# 01_-ATMEGA328.net
KiCad netlist of a schematic drawn in Altium Designer
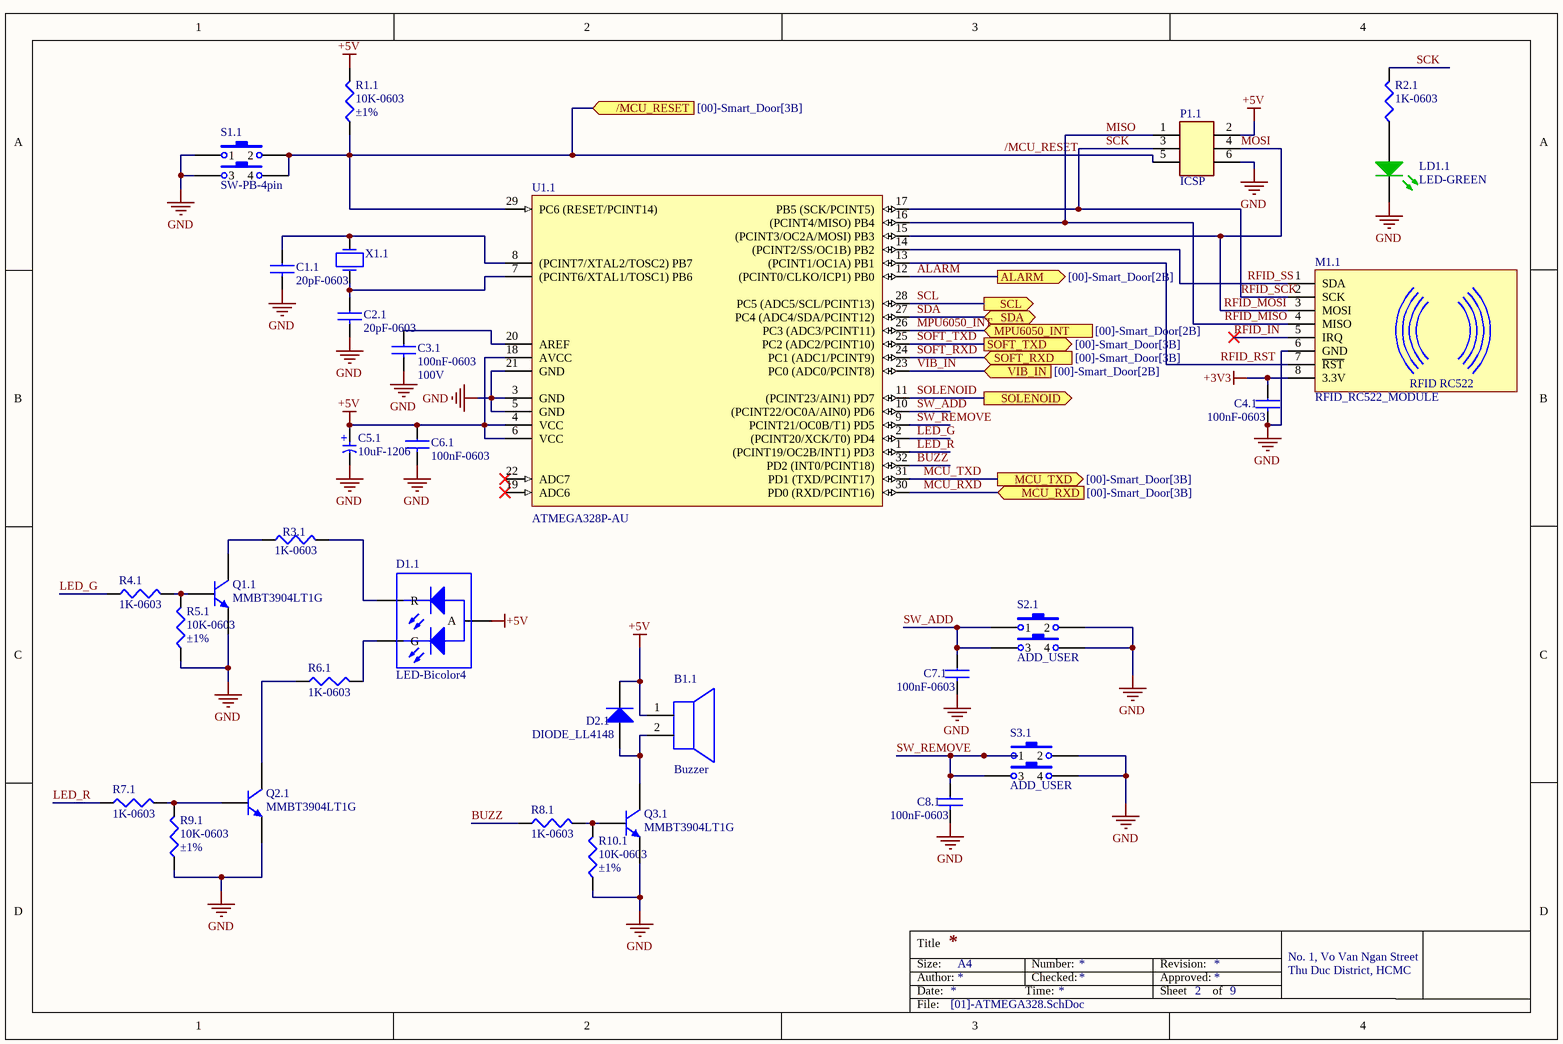
[diagram p0: [01]-ATMEGA328.SchDoc]

(export (version "E")
  (design (tool "Eeschema 10.0.6"))
  (components
    (comp (ref "B1.1")
      (value "Buzzer")
      (footprint "MinhTien_PcbLib:Buzzer")
      (libsource (lib "MinhTien_SCHLib") (part "Buzzer"))
    )
    (comp (ref "C1.1")
      (value "20pF-0603")
      (footprint "CAP0603")
      (description "CAP CER 20PF 50V C0G/NPO 0603")
      (fields (field (name "TOLERANCE") "±5%"))
      (libsource (lib "Indruino") (part "CC0603JRNPO9BN200"))
    )
    (comp (ref "C2.1")
      (value "20pF-0603")
      (footprint "CAP0603")
      (description "CAP CER 20PF 50V C0G/NPO 0603")
      (fields (field (name "TOLERANCE") "±5%"))
      (libsource (lib "Indruino") (part "CC0603JRNPO9BN200"))
    )
    (comp (ref "C3.1")
      (value "100nF-0603")
      (footprint "CAP0603")
      (description "CAP CER 0.1UF 100V X7R 0603")
      (fields
        (field (name "MANUFACTURER") "Yageo")
        (field (name "MANUFACTURER PART NUMBER") "CC0603KRX7R0BB104")
        (field (name "VOLTAGE - RATED") "100V")
      )
      (libsource (lib "Indruino") (part "CC0603KRX7R0BB104"))
    )
    (comp (ref "C4.1")
      (value "100nF-0603")
      (footprint "CAP0603")
      (description "CAP CER 0.1UF 50V X7R 0603")
      (fields (field (name "TOLERANCE") "±10%"))
      (libsource (lib "Indruino") (part "CC0603KRX7R9BB104"))
    )
    (comp (ref "C5.1")
      (value "10uF-1206")
      (footprint "AZ_Lib:CAP1206_TANT")
      (description "Cap Tant Solid 10uF 16V A CASE 10% (3.2 X 1.6 X 1.6mm) Inward L SMD 3216-18 3 Ohm 125C T/R")
      (fields (field (name "TOLERANCE") "10%") (field (name "VOLTAGE") "16V"))
      (libsource (lib "AZ_Lib") (part "T491A106K016AT"))
    )
    (comp (ref "C6.1")
      (value "100nF-0603")
      (footprint "CAP0603")
      (description "CAP CER 0.1UF 100V X7R 0603")
      (fields
        (field (name "MANUFACTURER") "Yageo")
        (field (name "MANUFACTURER PART NUMBER") "CC0603KRX7R0BB104")
      )
      (libsource (lib "Indruino") (part "CC0603KRX7R0BB104"))
    )
    (comp (ref "C7.1")
      (value "100nF-0603")
      (footprint "CAP0603")
      (description "CAP CER 0.1UF 50V X7R 0603")
      (fields (field (name "TOLERANCE") "±10%"))
      (libsource (lib "Indruino") (part "CC0603KRX7R9BB104"))
    )
    (comp (ref "C8.1")
      (value "100nF-0603")
      (footprint "CAP0603")
      (description "CAP CER 0.1UF 50V X7R 0603")
      (fields (field (name "TOLERANCE") "±10%"))
      (libsource (lib "Indruino") (part "CC0603KRX7R9BB104"))
    )
    (comp (ref "D1.1")
      (value "LED-Bicolor4")
      (footprint "MinhTien_PcbLib:LED_3mm-Bicolor")
      (description "Common Anode")
      (fields (field (name "PUBLISHER") "Altium Limited"))
      (libsource (lib "MinhTien_SCHLib") (part "LED-Bicolor4"))
    )
    (comp (ref "D2.1")
      (value "DIODE_LL4148")
      (footprint "Indruino:SOD80")
      (description "DIODE GEN PURP 100V 200MA SOD80")
      (fields
        (field (name "MANUFACTURER") "Fairchild/ON Semiconductor")
        (field (name "MANUFACTURER PART NUMBER") "LL4148")
      )
      (libsource (lib "Indruino") (part "DIODE_LL4148"))
    )
    (comp (ref "LD1.1")
      (value "LED-GREEN")
      (footprint "Indruino:LED_SMD0603_GREEN")
      (description "LED GREEN CLEAR 0603 SMD")
      (libsource (lib "Indruino") (part "LED_LTST-C191KGKT"))
    )
    (comp (ref "M1.1")
      (value "RFID_RC522_MODULE")
      (footprint "AZ_Lib:RFID_RC522_MODULE")
      (libsource (lib "AZ_Lib") (part "RFID_RC522_MODULE"))
    )
    (comp (ref "P1.1")
      (value "ICSP")
      (footprint "AZ_Lib:HDR3X2_2.54_MALE")
      (description "Header 3x2 pins male, pitch 2.54mm")
      (libsource (lib "AZ_Lib") (part "HDR3X2_2.54_MALE"))
    )
    (comp (ref "Q1.1")
      (value "MMBT3904LT1G")
      (footprint "Indruino:SOT23-3")
      (description "TRANS NPN 40V 0.2A SOT23")
      (libsource (lib "Indruino") (part "MMBT3904LT1G"))
    )
    (comp (ref "Q2.1")
      (value "MMBT3904LT1G")
      (footprint "Indruino:SOT23-3")
      (description "TRANS NPN 40V 0.2A SOT23")
      (libsource (lib "Indruino") (part "MMBT3904LT1G"))
    )
    (comp (ref "Q3.1")
      (value "MMBT3904LT1G")
      (footprint "Indruino:SOT23-3")
      (description "TRANS NPN 40V 0.2A SOT23")
      (libsource (lib "Indruino") (part "MMBT3904LT1G"))
    )
    (comp (ref "R1.1")
      (value "10K-0603")
      (footprint "RES0603")
      (description "RES SMD 10K OHM 1% 1/10W 0603")
      (fields
        (field (name "MANUFACTURER") "Yageo")
        (field (name "MANUFACTURER PART NUMBER") "RC0603FR-0710KL")
        (field (name "TOLERANCE") "±1%")
      )
      (libsource (lib "Indruino") (part "RC0603FR-0710KL"))
    )
    (comp (ref "R2.1")
      (value "1K-0603")
      (footprint "RES0603")
      (description "RES SMD 1K OHM 5% 1/10W 0603")
      (fields (field (name "TOLERANCE") "±5%"))
      (libsource (lib "Indruino") (part "RC0603JR-071KL"))
    )
    (comp (ref "R3.1")
      (value "1K-0603")
      (footprint "RES0603")
      (description "RES SMD 1K OHM 5% 1/10W 0603")
      (fields (field (name "TOLERANCE") "±5%"))
      (libsource (lib "Indruino") (part "RC0603JR-071KL"))
    )
    (comp (ref "R4.1")
      (value "1K-0603")
      (footprint "RES0603")
      (description "RES SMD 1K OHM 5% 1/10W 0603")
      (fields (field (name "TOLERANCE") "±5%"))
      (libsource (lib "Indruino") (part "RC0603JR-071KL"))
    )
    (comp (ref "R5.1")
      (value "10K-0603")
      (footprint "RES0603")
      (description "RES SMD 10K OHM 1% 1/10W 0603")
      (fields
        (field (name "MANUFACTURER") "Yageo")
        (field (name "MANUFACTURER PART NUMBER") "RC0603FR-0710KL")
        (field (name "TOLERANCE") "±1%")
      )
      (libsource (lib "Indruino") (part "RC0603FR-0710KL"))
    )
    (comp (ref "R6.1")
      (value "1K-0603")
      (footprint "RES0603")
      (description "RES SMD 1K OHM 5% 1/10W 0603")
      (fields (field (name "TOLERANCE") "±5%"))
      (libsource (lib "Indruino") (part "RC0603JR-071KL"))
    )
    (comp (ref "R7.1")
      (value "1K-0603")
      (footprint "RES0603")
      (description "RES SMD 1K OHM 5% 1/10W 0603")
      (fields (field (name "TOLERANCE") "±5%"))
      (libsource (lib "Indruino") (part "RC0603JR-071KL"))
    )
    (comp (ref "R8.1")
      (value "1K-0603")
      (footprint "RES0603")
      (description "RES SMD 1K OHM 5% 1/10W 0603")
      (fields (field (name "TOLERANCE") "±5%"))
      (libsource (lib "Indruino") (part "RC0603JR-071KL"))
    )
    (comp (ref "R9.1")
      (value "10K-0603")
      (footprint "RES0603")
      (description "RES SMD 10K OHM 1% 1/10W 0603")
      (fields
        (field (name "MANUFACTURER") "Yageo")
        (field (name "MANUFACTURER PART NUMBER") "RC0603FR-0710KL")
        (field (name "TOLERANCE") "±1%")
      )
      (libsource (lib "Indruino") (part "RC0603FR-0710KL"))
    )
    (comp (ref "R10.1")
      (value "10K-0603")
      (footprint "RES0603")
      (description "RES SMD 10K OHM 1% 1/10W 0603")
      (fields
        (field (name "MANUFACTURER") "Yageo")
        (field (name "MANUFACTURER PART NUMBER") "RC0603FR-0710KL")
        (field (name "TOLERANCE") "±1%")
      )
      (libsource (lib "Indruino") (part "RC0603FR-0710KL"))
    )
    (comp (ref "S1.1")
      (value "SW-PB-4pin")
      (footprint "MinhTien_PCBLib:SW4-KAN0647-0312B")
      (description "Switch")
      (fields (field (name "PUBLISHER") "Altium Limited"))
      (libsource (lib "MinhTien_SCHLib") (part "SW-PB-4pin"))
    )
    (comp (ref "S2.1")
      (value "ADD_USER")
      (footprint "MinhTien_PCBLib:SW4-KAN0647-0312B")
      (description "Switch")
      (fields (field (name "PUBLISHER") "Altium Limited"))
      (libsource (lib "MinhTien_SCHLib") (part "SW-PB-4pin"))
    )
    (comp (ref "S3.1")
      (value "ADD_USER")
      (footprint "MinhTien_PCBLib:SW4-KAN0647-0312B")
      (description "Switch")
      (fields (field (name "PUBLISHER") "Altium Limited"))
      (libsource (lib "MinhTien_SCHLib") (part "SW-PB-4pin"))
    )
    (comp (ref "U1.1")
      (value "ATMEGA328P-AU")
      (footprint "AZ_Lib:TQFP-32")
      (description "MICROCHIP - ATMEGA328P-AU. - MICROCONTROLLER MCU, 8 BIT, ATMEGA, 20MHZ, TQFP-32")
      (libsource (lib "AZ_Lib") (part "ATMEGA328P-AU"))
    )
    (comp (ref "X1.1")
      (value "9C-16.000MAAE-T")
      (footprint "XTAL_SMD_HC-49S")
      (description "CRYSTAL 16.0000MHZ 12PF SMD")
      (fields (field (name "MANUFACTURER") "TXC CORPORATION"))
      (libsource (lib "Indruino") (part "XTAL_9C-16.000MAAE-T"))
    )
  )
  (nets
    (net (code "1") (name "+3V3") (class "Default")
      (node (ref "C4.1") (pin "1") (pinfunction "1_1") (pintype "passive"))
      (node (ref "M1.1") (pin "8") (pinfunction "3.3V_8") (pintype "passive"))
    )
    (net (code "2") (name "+5V") (class "Default")
      (node (ref "B1.1") (pin "1") (pinfunction "+_1") (pintype "passive"))
      (node (ref "C5.1") (pin "1") (pinfunction "1_1") (pintype "passive"))
      (node (ref "C6.1") (pin "1") (pinfunction "1_1") (pintype "passive"))
      (node (ref "D1.1") (pin "2") (pinfunction "A_2") (pintype "passive"))
      (node (ref "D2.1") (pin "2") (pinfunction "K_2") (pintype "passive"))
      (node (ref "P1.1") (pin "2") (pinfunction "2_2") (pintype "passive"))
      (node (ref "R1.1") (pin "2") (pinfunction "2_2") (pintype "passive"))
      (node (ref "U1.1") (pin "18") (pinfunction "AVCC_18") (pintype "power_in"))
      (node (ref "U1.1") (pin "4") (pinfunction "VCC_4") (pintype "power_in"))
      (node (ref "U1.1") (pin "6") (pinfunction "VCC_6") (pintype "power_in"))
    )
    (net (code "3") (name "/ALARM") (class "Default")
      (node (ref "U1.1") (pin "12") (pinfunction "(PCINT0/CLKO/ICP1)_PB0_12") (pintype "bidirectional"))
    )
    (net (code "4") (name "/BUZZ") (class "Default")
      (node (ref "R8.1") (pin "1") (pinfunction "1_1") (pintype "passive"))
      (node (ref "U1.1") (pin "32") (pinfunction "PD2_(INT0/PCINT18)_32") (pintype "bidirectional"))
    )
    (net (code "5") (name "/LED_G") (class "Default")
      (node (ref "R4.1") (pin "1") (pinfunction "1_1") (pintype "passive"))
      (node (ref "U1.1") (pin "2") (pinfunction "(PCINT20/XCK/T0)_PD4_2") (pintype "bidirectional"))
    )
    (net (code "6") (name "/LED_R") (class "Default")
      (node (ref "R7.1") (pin "1") (pinfunction "1_1") (pintype "passive"))
      (node (ref "U1.1") (pin "1") (pinfunction "(PCINT19/OC2B/INT1)_PD3_1") (pintype "bidirectional"))
    )
    (net (code "7") (name "/MCU_RXD") (class "Default")
      (node (ref "U1.1") (pin "30") (pinfunction "PD0_(RXD/PCINT16)_30") (pintype "bidirectional"))
    )
    (net (code "8") (name "/MCU_TXD") (class "Default")
      (node (ref "U1.1") (pin "31") (pinfunction "PD1_(TXD/PCINT17)_31") (pintype "bidirectional"))
    )
    (net (code "9") (name "/MISO") (class "Default")
      (node (ref "M1.1") (pin "4") (pinfunction "MISO_4") (pintype "passive"))
      (node (ref "P1.1") (pin "1") (pinfunction "1_1") (pintype "passive"))
      (node (ref "U1.1") (pin "16") (pinfunction "(PCINT4/MISO)_PB4_16") (pintype "bidirectional"))
    )
    (net (code "10") (name "/MOSI") (class "Default")
      (node (ref "M1.1") (pin "3") (pinfunction "MOSI_3") (pintype "passive"))
      (node (ref "P1.1") (pin "4") (pinfunction "4_4") (pintype "passive"))
      (node (ref "U1.1") (pin "15") (pinfunction "(PCINT3/OC2A/MOSI)_PB3_15") (pintype "bidirectional"))
    )
    (net (code "11") (name "/MPU6050_INT") (class "Default")
      (node (ref "U1.1") (pin "26") (pinfunction "PC3_(ADC3/PCINT11)_26") (pintype "bidirectional"))
    )
    (net (code "12") (name "/RFID_IN") (class "Default")
      (node (ref "M1.1") (pin "5") (pinfunction "IRQ_5") (pintype "passive+no_connect"))
    )
    (net (code "13") (name "/RFID_RST") (class "Default")
      (node (ref "M1.1") (pin "7") (pinfunction "~{RST}_7") (pintype "passive"))
      (node (ref "U1.1") (pin "13") (pinfunction "(PCINT1/OC1A)_PB1_13") (pintype "bidirectional"))
    )
    (net (code "14") (name "/RFID_SCK") (class "Default")
      (node (ref "M1.1") (pin "2") (pinfunction "SCK_2") (pintype "passive"))
      (node (ref "P1.1") (pin "3") (pinfunction "3_3") (pintype "passive"))
      (node (ref "R2.1") (pin "2") (pinfunction "2_2") (pintype "passive"))
      (node (ref "U1.1") (pin "17") (pinfunction "PB5_(SCK/PCINT5)_17") (pintype "bidirectional"))
    )
    (net (code "15") (name "/RFID_SS") (class "Default")
      (node (ref "M1.1") (pin "1") (pinfunction "SDA_1") (pintype "passive"))
      (node (ref "U1.1") (pin "14") (pinfunction "(PCINT2/SS/OC1B)_PB2_14") (pintype "bidirectional"))
    )
    (net (code "16") (name "/SCL") (class "Default")
      (node (ref "U1.1") (pin "28") (pinfunction "PC5_(ADC5/SCL/PCINT13)_28") (pintype "bidirectional"))
    )
    (net (code "17") (name "/SDA") (class "Default")
      (node (ref "U1.1") (pin "27") (pinfunction "PC4_(ADC4/SDA/PCINT12)_27") (pintype "bidirectional"))
    )
    (net (code "18") (name "/SOFT_RXD") (class "Default")
      (node (ref "U1.1") (pin "24") (pinfunction "PC1_(ADC1/PCINT9)_24") (pintype "bidirectional"))
    )
    (net (code "19") (name "/SOFT_TXD") (class "Default")
      (node (ref "U1.1") (pin "25") (pinfunction "PC2_(ADC2/PCINT10)_25") (pintype "bidirectional"))
    )
    (net (code "20") (name "/SOLENOID") (class "Default")
      (node (ref "U1.1") (pin "11") (pinfunction "(PCINT23/AIN1)_PD7_11") (pintype "bidirectional"))
    )
    (net (code "21") (name "/SW_ADD") (class "Default")
      (node (ref "C7.1") (pin "1") (pinfunction "1_1") (pintype "passive"))
      (node (ref "S2.1") (pin "1") (pinfunction "1_1") (pintype "passive"))
      (node (ref "S2.1") (pin "3") (pinfunction "3_3") (pintype "passive"))
      (node (ref "U1.1") (pin "10") (pinfunction "(PCINT22/OC0A/AIN0)_PD6_10") (pintype "bidirectional"))
    )
    (net (code "22") (name "/SW_REMOVE") (class "Default")
      (node (ref "C8.1") (pin "1") (pinfunction "1_1") (pintype "passive"))
      (node (ref "S3.1") (pin "1") (pinfunction "1_1") (pintype "passive"))
      (node (ref "S3.1") (pin "3") (pinfunction "3_3") (pintype "passive"))
      (node (ref "U1.1") (pin "9") (pinfunction "PCINT21/OC0B/T1)_PD5_9") (pintype "bidirectional"))
    )
    (net (code "23") (name "/VIB_IN") (class "Default")
      (node (ref "U1.1") (pin "23") (pinfunction "PC0_(ADC0/PCINT8)_23") (pintype "bidirectional"))
    )
    (net (code "24") (name "/{slash}MCU_RESET") (class "Default")
      (node (ref "P1.1") (pin "5") (pinfunction "5_5") (pintype "passive"))
      (node (ref "R1.1") (pin "1") (pinfunction "1_1") (pintype "passive"))
      (node (ref "S1.1") (pin "2") (pinfunction "2_2") (pintype "passive"))
      (node (ref "S1.1") (pin "4") (pinfunction "4_4") (pintype "passive"))
      (node (ref "U1.1") (pin "29") (pinfunction "PC6_(RESET/PCINT14)_29") (pintype "input"))
    )
    (net (code "25") (name "GND") (class "Default")
      (node (ref "C1.1") (pin "2") (pinfunction "2_2") (pintype "passive"))
      (node (ref "C2.1") (pin "2") (pinfunction "2_2") (pintype "passive"))
      (node (ref "C3.1") (pin "2") (pinfunction "2_2") (pintype "passive"))
      (node (ref "C4.1") (pin "2") (pinfunction "2_2") (pintype "passive"))
      (node (ref "C5.1") (pin "2") (pinfunction "2_2") (pintype "passive"))
      (node (ref "C6.1") (pin "2") (pinfunction "2_2") (pintype "passive"))
      (node (ref "C7.1") (pin "2") (pinfunction "2_2") (pintype "passive"))
      (node (ref "C8.1") (pin "2") (pinfunction "2_2") (pintype "passive"))
      (node (ref "LD1.1") (pin "2") (pinfunction "K_2") (pintype "passive"))
      (node (ref "M1.1") (pin "6") (pinfunction "GND_6") (pintype "passive"))
      (node (ref "P1.1") (pin "6") (pinfunction "6_6") (pintype "passive"))
      (node (ref "Q1.1") (pin "2") (pinfunction "E_2") (pintype "passive"))
      (node (ref "Q2.1") (pin "2") (pinfunction "E_2") (pintype "passive"))
      (node (ref "Q3.1") (pin "2") (pinfunction "E_2") (pintype "passive"))
      (node (ref "R10.1") (pin "1") (pinfunction "1_1") (pintype "passive"))
      (node (ref "R5.1") (pin "1") (pinfunction "1_1") (pintype "passive"))
      (node (ref "R9.1") (pin "1") (pinfunction "1_1") (pintype "passive"))
      (node (ref "S1.1") (pin "1") (pinfunction "1_1") (pintype "passive"))
      (node (ref "S1.1") (pin "3") (pinfunction "3_3") (pintype "passive"))
      (node (ref "S2.1") (pin "2") (pinfunction "2_2") (pintype "passive"))
      (node (ref "S2.1") (pin "4") (pinfunction "4_4") (pintype "passive"))
      (node (ref "S3.1") (pin "2") (pinfunction "2_2") (pintype "passive"))
      (node (ref "S3.1") (pin "4") (pinfunction "4_4") (pintype "passive"))
      (node (ref "U1.1") (pin "21") (pinfunction "GND_21") (pintype "power_in"))
      (node (ref "U1.1") (pin "3") (pinfunction "GND_3") (pintype "power_in"))
      (node (ref "U1.1") (pin "5") (pinfunction "GND_5") (pintype "power_in"))
    )
    (net (code "26") (name "Net-(B1.1--)") (class "Default")
      (node (ref "B1.1") (pin "2") (pinfunction "-_2") (pintype "passive"))
      (node (ref "D2.1") (pin "1") (pinfunction "A_1") (pintype "passive"))
      (node (ref "Q3.1") (pin "3") (pinfunction "C_3") (pintype "passive"))
    )
    (net (code "27") (name "Net-(D1.1-G)") (class "Default")
      (node (ref "D1.1") (pin "1") (pinfunction "G_1") (pintype "passive"))
      (node (ref "R6.1") (pin "2") (pinfunction "2_2") (pintype "passive"))
    )
    (net (code "28") (name "Net-(D1.1-R)") (class "Default")
      (node (ref "D1.1") (pin "3") (pinfunction "R_3") (pintype "passive"))
      (node (ref "R3.1") (pin "2") (pinfunction "2_2") (pintype "passive"))
    )
    (net (code "29") (name "Net-(LD1.1-A)") (class "Default")
      (node (ref "LD1.1") (pin "1") (pinfunction "A_1") (pintype "passive"))
      (node (ref "R2.1") (pin "1") (pinfunction "1_1") (pintype "passive"))
    )
    (net (code "30") (name "Net-(Q1.1-B)") (class "Default")
      (node (ref "Q1.1") (pin "1") (pinfunction "B_1") (pintype "passive"))
      (node (ref "R4.1") (pin "2") (pinfunction "2_2") (pintype "passive"))
      (node (ref "R5.1") (pin "2") (pinfunction "2_2") (pintype "passive"))
    )
    (net (code "31") (name "Net-(Q1.1-C)") (class "Default")
      (node (ref "Q1.1") (pin "3") (pinfunction "C_3") (pintype "passive"))
      (node (ref "R3.1") (pin "1") (pinfunction "1_1") (pintype "passive"))
    )
    (net (code "32") (name "Net-(Q2.1-B)") (class "Default")
      (node (ref "Q2.1") (pin "1") (pinfunction "B_1") (pintype "passive"))
      (node (ref "R7.1") (pin "2") (pinfunction "2_2") (pintype "passive"))
      (node (ref "R9.1") (pin "2") (pinfunction "2_2") (pintype "passive"))
    )
    (net (code "33") (name "Net-(Q2.1-C)") (class "Default")
      (node (ref "Q2.1") (pin "3") (pinfunction "C_3") (pintype "passive"))
      (node (ref "R6.1") (pin "1") (pinfunction "1_1") (pintype "passive"))
    )
    (net (code "34") (name "Net-(Q3.1-B)") (class "Default")
      (node (ref "Q3.1") (pin "1") (pinfunction "B_1") (pintype "passive"))
      (node (ref "R10.1") (pin "2") (pinfunction "2_2") (pintype "passive"))
      (node (ref "R8.1") (pin "2") (pinfunction "2_2") (pintype "passive"))
    )
    (net (code "35") (name "Net-(U1.1-(PCINT6{slash}XTAL1{slash}TOSC1)_PB6)") (class "Default")
      (node (ref "C2.1") (pin "1") (pinfunction "1_1") (pintype "passive"))
      (node (ref "U1.1") (pin "7") (pinfunction "(PCINT6/XTAL1/TOSC1)_PB6_7") (pintype "passive"))
      (node (ref "X1.1") (pin "1") (pinfunction "OSC1_1") (pintype "passive"))
    )
    (net (code "36") (name "Net-(U1.1-(PCINT7{slash}XTAL2{slash}TOSC2)_PB7)") (class "Default")
      (node (ref "C1.1") (pin "1") (pinfunction "1_1") (pintype "passive"))
      (node (ref "U1.1") (pin "8") (pinfunction "(PCINT7/XTAL2/TOSC2)_PB7_8") (pintype "passive"))
      (node (ref "X1.1") (pin "2") (pinfunction "OSC2_2") (pintype "passive"))
    )
    (net (code "37") (name "Net-(U1.1-AREF)") (class "Default")
      (node (ref "C3.1") (pin "1") (pinfunction "1_1") (pintype "passive"))
      (node (ref "U1.1") (pin "20") (pinfunction "AREF_20") (pintype "power_in"))
    )
    (net (code "38") (name "unconnected-(U1.1-ADC6-Pad19)") (class "Default")
      (node (ref "U1.1") (pin "19") (pinfunction "ADC6_19") (pintype "input+no_connect"))
    )
    (net (code "39") (name "unconnected-(U1.1-ADC7-Pad22)") (class "Default")
      (node (ref "U1.1") (pin "22") (pinfunction "ADC7_22") (pintype "input+no_connect"))
    )
  )
)
